# conrad.net
KiCad netlist of a schematic drawn in EAGLE
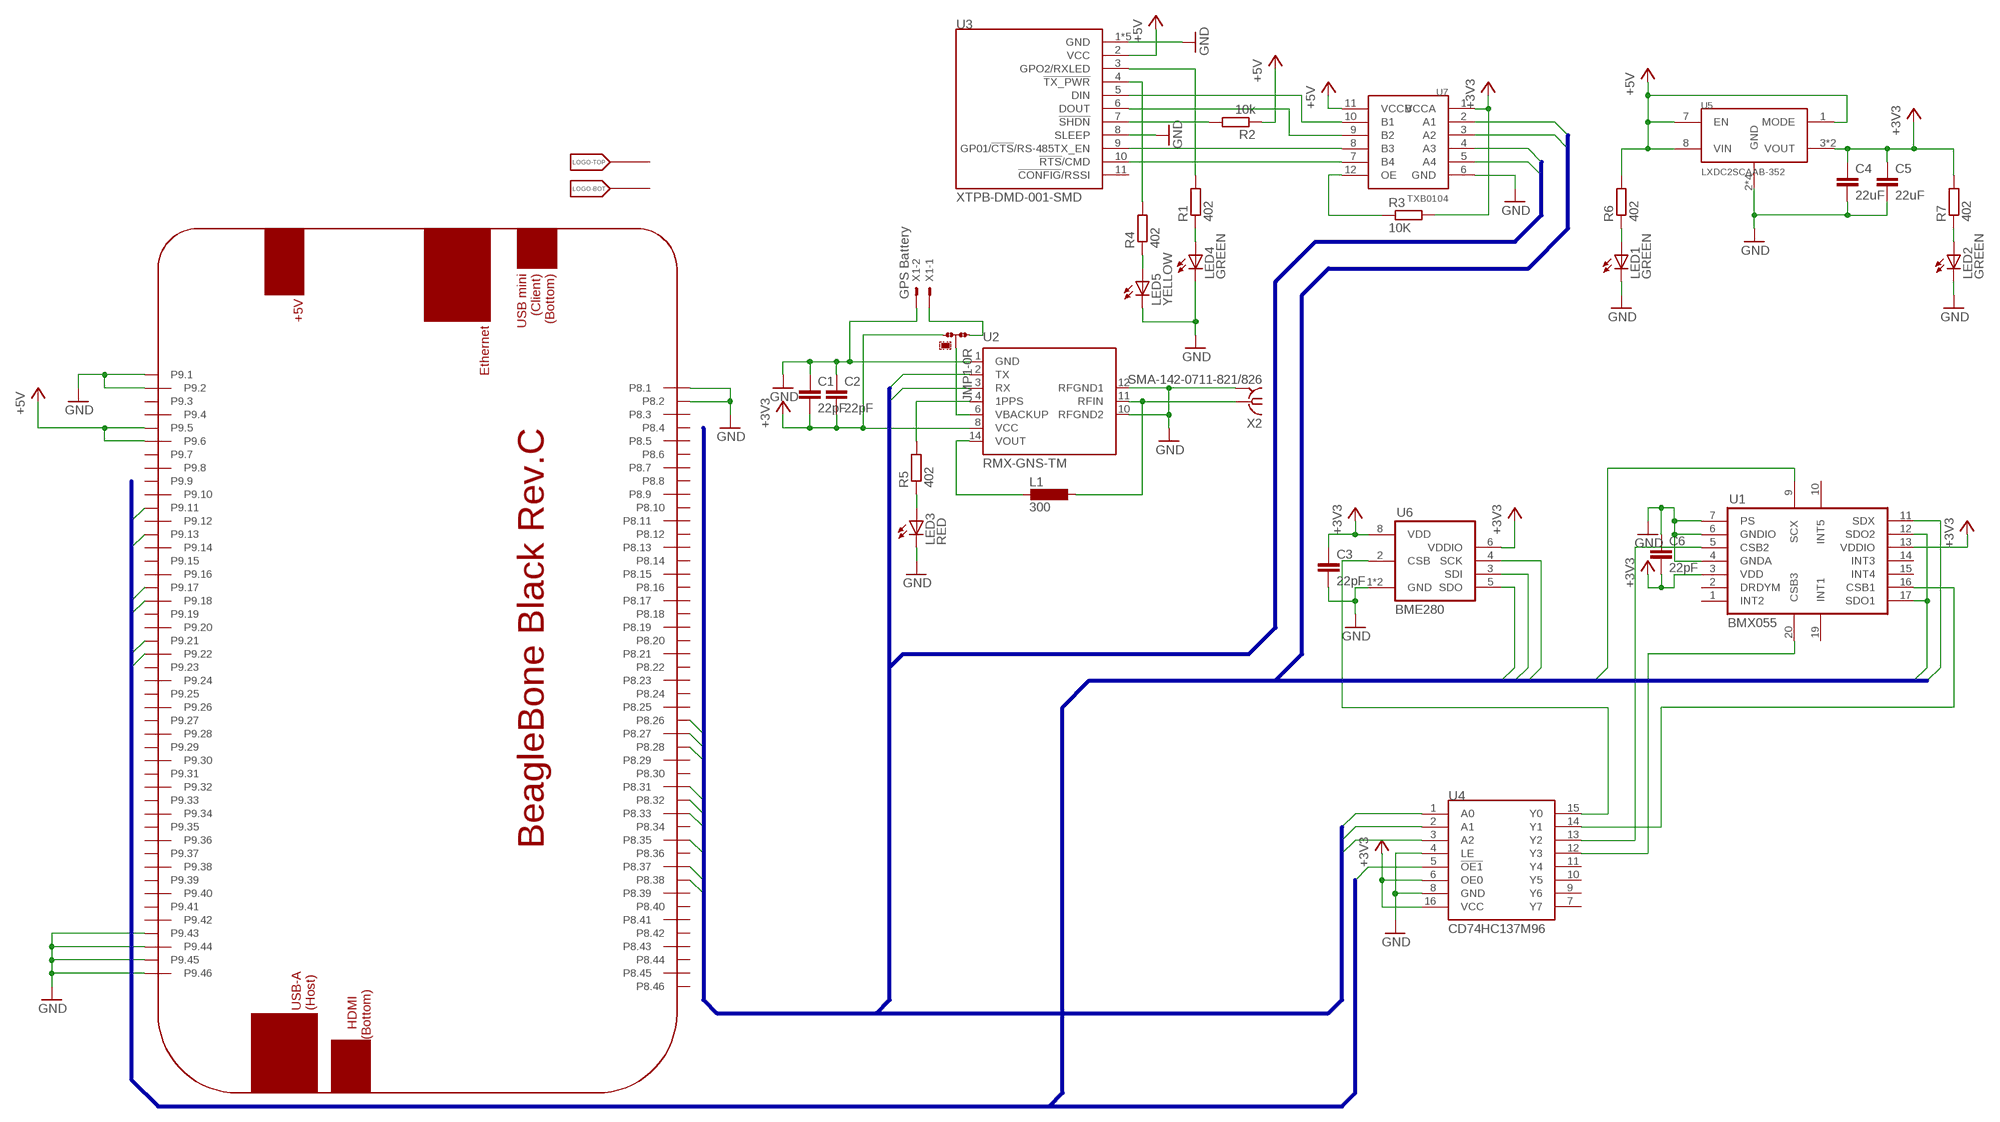
[diagram p0: schematic, sheet 1]

(export (version "E")
  (design (tool "Eeschema 10.0.6"))
  (components
    (comp (ref "C1")
      (value "22pF")
      (footprint "eagle-import:C0603K")
      (libsource (lib "eagle-import") (part "C-EUC0603K"))
    )
    (comp (ref "C2")
      (value "22pF")
      (footprint "eagle-import:C0603K")
      (libsource (lib "eagle-import") (part "C-EUC0603K"))
    )
    (comp (ref "C3")
      (value "22pF")
      (footprint "eagle-import:C0603K")
      (libsource (lib "eagle-import") (part "C-EUC0603K"))
    )
    (comp (ref "C4")
      (value "22uF")
      (footprint "eagle-import:C0603K")
      (libsource (lib "eagle-import") (part "C-EUC0603K"))
    )
    (comp (ref "C5")
      (value "22uF")
      (footprint "eagle-import:C0603K")
      (libsource (lib "eagle-import") (part "C-EUC0603K"))
    )
    (comp (ref "C6")
      (value "22pF")
      (footprint "eagle-import:C0603K")
      (libsource (lib "eagle-import") (part "C-EUC0603K"))
    )
    (comp (ref "JMP1")
      (value "0R-JUMPB")
      (footprint "eagle-import:B0R-JMP")
      (libsource (lib "eagle-import") (part "0R-JUMPB"))
    )
    (comp (ref "L1")
      (value "300")
      (footprint "eagle-import:L0402")
      (libsource (lib "eagle-import") (part "L-EU"))
    )
    (comp (ref "LED1")
      (value "GREEN")
      (footprint "eagle-import:SML0805")
      (libsource (lib "eagle-import") (part "LEDSML0805"))
    )
    (comp (ref "LED2")
      (value "GREEN")
      (footprint "eagle-import:SML0805")
      (libsource (lib "eagle-import") (part "LEDSML0805"))
    )
    (comp (ref "LED3")
      (value "RED")
      (footprint "eagle-import:SML0805")
      (libsource (lib "eagle-import") (part "LEDSML0805"))
    )
    (comp (ref "LED4")
      (value "GREEN")
      (footprint "eagle-import:SML0805")
      (libsource (lib "eagle-import") (part "LEDSML0805"))
    )
    (comp (ref "LED5")
      (value "YELLOW")
      (footprint "eagle-import:SML0805")
      (libsource (lib "eagle-import") (part "LEDSML0805"))
    )
    (comp (ref "LOGO")
      (value "SU_LOGO-DUMMY")
      (footprint "eagle-import:SU_LOGO_DS")
      (libsource (lib "eagle-import") (part "SU_LOGO-DUMMY"))
    )
    (comp (ref "PCB1")
      (value "BEAGLEBONE_BLACK_CAPE")
      (footprint "eagle-import:BEAGLEBONE_BLACK_CAPE")
      (libsource (lib "eagle-import") (part "BEAGLEBONE_BLACK_CAPE"))
    )
    (comp (ref "R1")
      (value "402")
      (footprint "eagle-import:R0603")
      (libsource (lib "eagle-import") (part "R-EU_R0603"))
    )
    (comp (ref "R2")
      (value "10k")
      (footprint "eagle-import:R0603")
      (libsource (lib "eagle-import") (part "R-EU_R0603"))
    )
    (comp (ref "R3")
      (value "10K")
      (footprint "eagle-import:R0603")
      (libsource (lib "eagle-import") (part "R-EU_R0603"))
    )
    (comp (ref "R4")
      (value "402")
      (footprint "eagle-import:R0603")
      (libsource (lib "eagle-import") (part "R-EU_R0603"))
    )
    (comp (ref "R5")
      (value "402")
      (footprint "eagle-import:R0603")
      (libsource (lib "eagle-import") (part "R-EU_R0603"))
    )
    (comp (ref "R6")
      (value "402")
      (footprint "eagle-import:R0603")
      (libsource (lib "eagle-import") (part "R-EU_R0603"))
    )
    (comp (ref "R7")
      (value "402")
      (footprint "eagle-import:R0603")
      (libsource (lib "eagle-import") (part "R-EU_R0603"))
    )
    (comp (ref "U1")
      (value "BMX055")
      (footprint "eagle-import:BMX055")
      (libsource (lib "eagle-import") (part "BMX055"))
    )
    (comp (ref "U2")
      (value "RMX-GNS-TM")
      (footprint "eagle-import:RMX-GNSS-TM")
      (libsource (lib "eagle-import") (part "RMX-GNS-TM"))
    )
    (comp (ref "U3")
      (value "XTPB-DMD-001-SMD")
      (footprint "eagle-import:XTP9B-DMS-001-SMD")
      (libsource (lib "eagle-import") (part "XTPB-DMD-001-SMD"))
    )
    (comp (ref "U4")
      (value "CD74HC137M96")
      (footprint "eagle-import:SO-16")
      (libsource (lib "eagle-import") (part "CD74HC237M96"))
    )
    (comp (ref "U5")
      (value "LXDC2SCAAB-352")
      (footprint "eagle-import:LXDC2SCAAB-352")
      (libsource (lib "eagle-import") (part "LXDC2SCAAB-352"))
    )
    (comp (ref "U6")
      (value "BME280")
      (footprint "eagle-import:BME280")
      (libsource (lib "eagle-import") (part "BME280"))
    )
    (comp (ref "U7")
      (value "TXB0104")
      (footprint "eagle-import:R-PUQFN-N12")
      (libsource (lib "eagle-import") (part "TXB0104"))
    )
    (comp (ref "X1")
      (value "GPS Battery")
      (footprint "eagle-import:15-91-02")
      (libsource (lib "eagle-import") (part "C-GRID-02-15-19"))
    )
    (comp (ref "X2")
      (value "SMA-142-0711-821/826")
      (footprint "eagle-import:J502-ND-142-0711-821_826")
      (fields (field (name "MF") "JOHNSON COMPONENTS") (field (name "MPN") "142-0711-821"))
      (libsource (lib "eagle-import") (part "SMA-142-0711-821/826"))
    )
  )
  (nets
    (net (code "1") (name "+3V3") (class "Default")
      (node (ref "C1") (pin "2") (pinfunction "2_2") (pintype "passive"))
      (node (ref "C2") (pin "2") (pinfunction "2_2") (pintype "passive"))
      (node (ref "C3") (pin "1") (pinfunction "1_1") (pintype "passive"))
      (node (ref "C4") (pin "1") (pinfunction "1_1") (pintype "passive"))
      (node (ref "C5") (pin "1") (pinfunction "1_1") (pintype "passive"))
      (node (ref "C6") (pin "2") (pinfunction "2_2") (pintype "passive"))
      (node (ref "JMP1") (pin "3") (pinfunction "3_3") (pintype "passive"))
      (node (ref "R3") (pin "2") (pinfunction "2_2") (pintype "passive"))
      (node (ref "R7") (pin "2") (pinfunction "2_2") (pintype "passive"))
      (node (ref "U1") (pin "13") (pinfunction "VDDIO_13") (pintype "power_in"))
      (node (ref "U1") (pin "3") (pinfunction "VDD_3") (pintype "power_in"))
      (node (ref "U2") (pin "8") (pinfunction "VCC_8") (pintype "power_in"))
      (node (ref "U4") (pin "16") (pinfunction "VCC_16") (pintype "power_in"))
      (node (ref "U4") (pin "6") (pinfunction "OE0_6") (pintype "input"))
      (node (ref "U5") (pin "3") (pinfunction "VOUT_3") (pintype "power_in"))
      (node (ref "U5") (pin "4") (pinfunction "VOUT_4") (pintype "power_in"))
      (node (ref "U6") (pin "6") (pinfunction "VDDIO_6") (pintype "power_in"))
      (node (ref "U6") (pin "8") (pinfunction "VDD_8") (pintype "power_in"))
      (node (ref "U7") (pin "1") (pinfunction "VCCA_1") (pintype "power_in"))
    )
    (net (code "2") (name "+5V") (class "Default")
      (node (ref "PCB1") (pin "P9.5") (pinfunction "P9.5_P9.5") (pintype "bidirectional"))
      (node (ref "PCB1") (pin "P9.6") (pinfunction "P9.6_P9.6") (pintype "bidirectional"))
      (node (ref "R2") (pin "1") (pinfunction "1_1") (pintype "passive"))
      (node (ref "R6") (pin "2") (pinfunction "2_2") (pintype "passive"))
      (node (ref "U3") (pin "2") (pinfunction "VCC_2") (pintype "power_in"))
      (node (ref "U5") (pin "1") (pinfunction "MODE_1") (pintype "input"))
      (node (ref "U5") (pin "7") (pinfunction "EN_7") (pintype "input"))
      (node (ref "U5") (pin "8") (pinfunction "VIN_8") (pintype "power_in"))
      (node (ref "U7") (pin "11") (pinfunction "VCCB_11") (pintype "power_in"))
    )
    (net (code "3") (name "/SPI0_CS0") (class "Default")
      (node (ref "PCB1") (pin "P9.17") (pinfunction "P9.17_P9.17") (pintype "bidirectional"))
      (node (ref "U4") (pin "5") (pinfunction "~{OE1}_5") (pintype "input"))
    )
    (net (code "4") (name "/SPI0_D0") (class "Default")
      (node (ref "PCB1") (pin "P9.21") (pinfunction "P9.21_P9.21") (pintype "bidirectional"))
      (node (ref "U1") (pin "12") (pinfunction "SDO2_12") (pintype "output"))
      (node (ref "U1") (pin "17") (pinfunction "SDO1_17") (pintype "output"))
      (node (ref "U6") (pin "5") (pinfunction "SDO_5") (pintype "input"))
    )
    (net (code "5") (name "/SPI0_D1") (class "Default")
      (node (ref "PCB1") (pin "P9.18") (pinfunction "P9.18_P9.18") (pintype "bidirectional"))
      (node (ref "U1") (pin "11") (pinfunction "SDX_11") (pintype "bidirectional"))
      (node (ref "U6") (pin "3") (pinfunction "SDI_3") (pintype "bidirectional"))
    )
    (net (code "6") (name "/SPI0_SCLK") (class "Default")
      (node (ref "PCB1") (pin "P9.22") (pinfunction "P9.22_P9.22") (pintype "bidirectional"))
      (node (ref "U1") (pin "9") (pinfunction "SCX_9") (pintype "input"))
      (node (ref "U6") (pin "4") (pinfunction "SCK_4") (pintype "bidirectional"))
    )
    (net (code "7") (name "/SPI_CSB26") (class "Default")
      (node (ref "PCB1") (pin "P8.26") (pinfunction "P8.26_P8.26") (pintype "bidirectional"))
      (node (ref "U4") (pin "1") (pinfunction "A0_1") (pintype "input"))
    )
    (net (code "8") (name "/SPI_CSB27") (class "Default")
      (node (ref "PCB1") (pin "P8.27") (pinfunction "P8.27_P8.27") (pintype "bidirectional"))
      (node (ref "U4") (pin "2") (pinfunction "A1_2") (pintype "input"))
    )
    (net (code "9") (name "/SPI_CSB28") (class "Default")
      (node (ref "PCB1") (pin "P8.28") (pinfunction "P8.28_P8.28") (pintype "bidirectional"))
      (node (ref "U4") (pin "3") (pinfunction "A2_3") (pintype "input"))
    )
    (net (code "10") (name "/UART4_CTSN") (class "Default")
      (node (ref "PCB1") (pin "P8.35") (pinfunction "P8.35_P8.35") (pintype "bidirectional"))
      (node (ref "U7") (pin "4") (pinfunction "A3_4") (pintype "bidirectional"))
    )
    (net (code "11") (name "/UART4_RTSN") (class "Default")
      (node (ref "PCB1") (pin "P8.33") (pinfunction "P8.33_P8.33") (pintype "bidirectional"))
      (node (ref "U7") (pin "5") (pinfunction "A4_5") (pintype "bidirectional"))
    )
    (net (code "12") (name "/UART4_RXD") (class "Default")
      (node (ref "PCB1") (pin "P9.11") (pinfunction "P9.11_P9.11") (pintype "bidirectional"))
      (node (ref "U7") (pin "3") (pinfunction "A2_3") (pintype "bidirectional"))
    )
    (net (code "13") (name "/UART4_TXD") (class "Default")
      (node (ref "PCB1") (pin "P9.13") (pinfunction "P9.13_P9.13") (pintype "bidirectional"))
      (node (ref "U7") (pin "2") (pinfunction "A1_2") (pintype "bidirectional"))
    )
    (net (code "14") (name "/UART5_RXD") (class "Default")
      (node (ref "PCB1") (pin "P8.38") (pinfunction "P8.38_P8.38") (pintype "bidirectional"))
      (node (ref "U2") (pin "2") (pinfunction "TX_2") (pintype "output"))
    )
    (net (code "15") (name "/UART5_TXD") (class "Default")
      (node (ref "PCB1") (pin "P8.37") (pinfunction "P8.37_P8.37") (pintype "bidirectional"))
      (node (ref "U2") (pin "3") (pinfunction "RX_3") (pintype "input"))
    )
    (net (code "16") (name "GND") (class "Default")
      (node (ref "C1") (pin "1") (pinfunction "1_1") (pintype "passive"))
      (node (ref "C2") (pin "1") (pinfunction "1_1") (pintype "passive"))
      (node (ref "C3") (pin "2") (pinfunction "2_2") (pintype "passive"))
      (node (ref "C4") (pin "2") (pinfunction "2_2") (pintype "passive"))
      (node (ref "C5") (pin "2") (pinfunction "2_2") (pintype "passive"))
      (node (ref "C6") (pin "1") (pinfunction "1_1") (pintype "passive"))
      (node (ref "LED1") (pin "C") (pinfunction "C_C") (pintype "passive"))
      (node (ref "LED2") (pin "C") (pinfunction "C_C") (pintype "passive"))
      (node (ref "LED3") (pin "C") (pinfunction "C_C") (pintype "passive"))
      (node (ref "LED4") (pin "C") (pinfunction "C_C") (pintype "passive"))
      (node (ref "LED5") (pin "C") (pinfunction "C_C") (pintype "passive"))
      (node (ref "PCB1") (pin "P8.1") (pinfunction "P8.1_P8.1") (pintype "bidirectional"))
      (node (ref "PCB1") (pin "P8.2") (pinfunction "P8.2_P8.2") (pintype "bidirectional"))
      (node (ref "PCB1") (pin "P9.1") (pinfunction "P9.1_P9.1") (pintype "bidirectional"))
      (node (ref "PCB1") (pin "P9.2") (pinfunction "P9.2_P9.2") (pintype "bidirectional"))
      (node (ref "PCB1") (pin "P9.43") (pinfunction "P9.43_P9.43") (pintype "bidirectional"))
      (node (ref "PCB1") (pin "P9.44") (pinfunction "P9.44_P9.44") (pintype "bidirectional"))
      (node (ref "PCB1") (pin "P9.45") (pinfunction "P9.45_P9.45") (pintype "bidirectional"))
      (node (ref "PCB1") (pin "P9.46") (pinfunction "P9.46_P9.46") (pintype "bidirectional"))
      (node (ref "U1") (pin "4") (pinfunction "GNDA_4") (pintype "power_in"))
      (node (ref "U1") (pin "6") (pinfunction "GNDIO_6") (pintype "bidirectional"))
      (node (ref "U1") (pin "7") (pinfunction "PS_7") (pintype "input"))
      (node (ref "U2") (pin "1") (pinfunction "GND_1") (pintype "power_in"))
      (node (ref "U2") (pin "10") (pinfunction "RFGND2_10") (pintype "power_in"))
      (node (ref "U2") (pin "12") (pinfunction "RFGND1_12") (pintype "power_in"))
      (node (ref "U3") (pin "1") (pinfunction "GND_1") (pintype "power_in"))
      (node (ref "U3") (pin "8") (pinfunction "SLEEP_8") (pintype "input"))
      (node (ref "U3") (pin "P$1") (pinfunction "GND_P$1") (pintype "power_in"))
      (node (ref "U3") (pin "P$2") (pinfunction "GND_P$2") (pintype "power_in"))
      (node (ref "U3") (pin "P$3") (pinfunction "GND_P$3") (pintype "power_in"))
      (node (ref "U3") (pin "P$4") (pinfunction "GND_P$4") (pintype "power_in"))
      (node (ref "U4") (pin "4") (pinfunction "LE_4") (pintype "input"))
      (node (ref "U4") (pin "8") (pinfunction "GND_8") (pintype "power_in"))
      (node (ref "U5") (pin "2") (pinfunction "GND_2") (pintype "power_in"))
      (node (ref "U5") (pin "5") (pinfunction "GND_5") (pintype "power_in"))
      (node (ref "U5") (pin "6") (pinfunction "GND_6") (pintype "power_in"))
      (node (ref "U5") (pin "9") (pinfunction "GND_9") (pintype "power_in"))
      (node (ref "U6") (pin "1") (pinfunction "GND_1") (pintype "power_in"))
      (node (ref "U6") (pin "7") (pinfunction "GND_7") (pintype "power_in"))
      (node (ref "U7") (pin "6") (pinfunction "GND_6") (pintype "power_in"))
      (node (ref "X1") (pin "2") (pinfunction "S_2") (pintype "passive"))
      (node (ref "X2") (pin "G@1") (pinfunction "2_G@1") (pintype "passive"))
      (node (ref "X2") (pin "G@2") (pinfunction "2_G@2") (pintype "passive"))
      (node (ref "X2") (pin "G@3") (pinfunction "2_G@3") (pintype "passive"))
      (node (ref "X2") (pin "G@4") (pinfunction "2_G@4") (pintype "passive"))
    )
    (net (code "17") (name "Net-(LED1-PadA)") (class "Default")
      (node (ref "LED1") (pin "A") (pinfunction "A_A") (pintype "passive"))
      (node (ref "R6") (pin "1") (pinfunction "1_1") (pintype "passive"))
    )
    (net (code "18") (name "Net-(LED2-PadA)") (class "Default")
      (node (ref "LED2") (pin "A") (pinfunction "A_A") (pintype "passive"))
      (node (ref "R7") (pin "1") (pinfunction "1_1") (pintype "passive"))
    )
    (net (code "19") (name "Net-(LED3-PadA)") (class "Default")
      (node (ref "LED3") (pin "A") (pinfunction "A_A") (pintype "passive"))
      (node (ref "R5") (pin "1") (pinfunction "1_1") (pintype "passive"))
    )
    (net (code "20") (name "Net-(LED4-PadA)") (class "Default")
      (node (ref "LED4") (pin "A") (pinfunction "A_A") (pintype "passive"))
      (node (ref "R1") (pin "1") (pinfunction "1_1") (pintype "passive"))
    )
    (net (code "21") (name "Net-(LED5-PadA)") (class "Default")
      (node (ref "LED5") (pin "A") (pinfunction "A_A") (pintype "passive"))
      (node (ref "R4") (pin "1") (pinfunction "1_1") (pintype "passive"))
    )
    (net (code "22") (name "Net-(U1-CSB1)") (class "Default")
      (node (ref "U1") (pin "16") (pinfunction "CSB1_16") (pintype "input"))
      (node (ref "U4") (pin "14") (pinfunction "Y1_14") (pintype "output"))
    )
    (net (code "23") (name "Net-(U1-CSB2)") (class "Default")
      (node (ref "U1") (pin "5") (pinfunction "CSB2_5") (pintype "input"))
      (node (ref "U4") (pin "13") (pinfunction "Y2_13") (pintype "output"))
    )
    (net (code "24") (name "Net-(U1-CSB3)") (class "Default")
      (node (ref "U1") (pin "20") (pinfunction "CSB3_20") (pintype "input"))
      (node (ref "U4") (pin "12") (pinfunction "Y3_12") (pintype "output"))
    )
    (net (code "25") (name "Net-(U2-1PPS)") (class "Default")
      (node (ref "R5") (pin "2") (pinfunction "2_2") (pintype "passive"))
      (node (ref "U2") (pin "4") (pinfunction "1PPS_4") (pintype "output"))
    )
    (net (code "26") (name "Net-(U2-RFIN)") (class "Default")
      (node (ref "L1") (pin "1") (pinfunction "1_1") (pintype "passive"))
      (node (ref "U2") (pin "11") (pinfunction "RFIN_11") (pintype "input"))
      (node (ref "X2") (pin "1") (pinfunction "1_1") (pintype "passive"))
    )
    (net (code "27") (name "Net-(U2-VBACKUP)") (class "Default")
      (node (ref "JMP1") (pin "2") (pinfunction "2_2") (pintype "passive"))
      (node (ref "U2") (pin "6") (pinfunction "VBACKUP_6") (pintype "power_in"))
    )
    (net (code "28") (name "Net-(U2-VOUT)") (class "Default")
      (node (ref "L1") (pin "2") (pinfunction "2_2") (pintype "passive"))
      (node (ref "U2") (pin "14") (pinfunction "VOUT_14") (pintype "output"))
    )
    (net (code "29") (name "Net-(U3-DIN)") (class "Default")
      (node (ref "U3") (pin "5") (pinfunction "DIN_5") (pintype "input"))
      (node (ref "U7") (pin "10") (pinfunction "B1_10") (pintype "bidirectional"))
    )
    (net (code "30") (name "Net-(U3-DOUT)") (class "Default")
      (node (ref "U3") (pin "6") (pinfunction "DOUT_6") (pintype "output"))
      (node (ref "U7") (pin "9") (pinfunction "B2_9") (pintype "bidirectional"))
    )
    (net (code "31") (name "Net-(U3-GP01{slash}~{CTS}{slash}RS-485TX_EN)") (class "Default")
      (node (ref "U3") (pin "9") (pinfunction "GP01/~{CTS}/RS-485TX_EN_9") (pintype "output"))
      (node (ref "U7") (pin "8") (pinfunction "B3_8") (pintype "bidirectional"))
    )
    (net (code "32") (name "Net-(U3-GPO2{slash}RXLED)") (class "Default")
      (node (ref "R1") (pin "2") (pinfunction "2_2") (pintype "passive"))
      (node (ref "U3") (pin "3") (pinfunction "GPO2/RXLED_3") (pintype "output"))
    )
    (net (code "33") (name "Net-(U3-~{RTS}{slash}CMD)") (class "Default")
      (node (ref "U3") (pin "10") (pinfunction "~{RTS}/CMD_10") (pintype "input"))
      (node (ref "U7") (pin "7") (pinfunction "B4_7") (pintype "bidirectional"))
    )
    (net (code "34") (name "Net-(U3-~{SHDN})") (class "Default")
      (node (ref "R2") (pin "2") (pinfunction "2_2") (pintype "passive"))
      (node (ref "U3") (pin "7") (pinfunction "~{SHDN}_7") (pintype "input"))
    )
    (net (code "35") (name "Net-(U3-~{TX_PWR})") (class "Default")
      (node (ref "R4") (pin "2") (pinfunction "2_2") (pintype "passive"))
      (node (ref "U3") (pin "4") (pinfunction "~{TX_PWR}_4") (pintype "output"))
    )
    (net (code "36") (name "Net-(U4-Y0)") (class "Default")
      (node (ref "U4") (pin "15") (pinfunction "Y0_15") (pintype "output"))
      (node (ref "U6") (pin "2") (pinfunction "CSB_2") (pintype "input"))
    )
    (net (code "37") (name "Net-(U7-OE)") (class "Default")
      (node (ref "R3") (pin "1") (pinfunction "1_1") (pintype "passive"))
      (node (ref "U7") (pin "12") (pinfunction "OE_12") (pintype "input"))
    )
    (net (code "38") (name "Net-(X1A-S)") (class "Default")
      (node (ref "JMP1") (pin "1") (pinfunction "1_1") (pintype "passive"))
      (node (ref "X1") (pin "1") (pinfunction "S_1") (pintype "passive"))
    )
    (net (code "39") (name "unconnected-(LOGO-PadP$1)") (class "Default")
      (node (ref "LOGO") (pin "P$1") (pinfunction "P$1_P$1") (pintype "bidirectional"))
    )
    (net (code "40") (name "unconnected-(LOGOA-P$1-PadP$2)") (class "Default")
      (node (ref "LOGO") (pin "P$2") (pinfunction "P$1_P$2") (pintype "bidirectional"))
    )
    (net (code "41") (name "unconnected-(PCB1-PadP8.3)") (class "Default")
      (node (ref "PCB1") (pin "P8.3") (pinfunction "P8.3_P8.3") (pintype "bidirectional"))
    )
    (net (code "42") (name "unconnected-(PCB1-PadP8.4)") (class "Default")
      (node (ref "PCB1") (pin "P8.4") (pinfunction "P8.4_P8.4") (pintype "bidirectional"))
    )
    (net (code "43") (name "unconnected-(PCB1-PadP8.5)") (class "Default")
      (node (ref "PCB1") (pin "P8.5") (pinfunction "P8.5_P8.5") (pintype "bidirectional"))
    )
    (net (code "44") (name "unconnected-(PCB1-PadP8.6)") (class "Default")
      (node (ref "PCB1") (pin "P8.6") (pinfunction "P8.6_P8.6") (pintype "bidirectional"))
    )
    (net (code "45") (name "unconnected-(PCB1-PadP8.7)") (class "Default")
      (node (ref "PCB1") (pin "P8.7") (pinfunction "P8.7_P8.7") (pintype "bidirectional"))
    )
    (net (code "46") (name "unconnected-(PCB1-PadP8.8)") (class "Default")
      (node (ref "PCB1") (pin "P8.8") (pinfunction "P8.8_P8.8") (pintype "bidirectional"))
    )
    (net (code "47") (name "unconnected-(PCB1-PadP8.9)") (class "Default")
      (node (ref "PCB1") (pin "P8.9") (pinfunction "P8.9_P8.9") (pintype "bidirectional"))
    )
    (net (code "48") (name "unconnected-(PCB1-PadP8.10)") (class "Default")
      (node (ref "PCB1") (pin "P8.10") (pinfunction "P8.10_P8.10") (pintype "bidirectional"))
    )
    (net (code "49") (name "unconnected-(PCB1-PadP8.11)") (class "Default")
      (node (ref "PCB1") (pin "P8.11") (pinfunction "P8.11_P8.11") (pintype "bidirectional"))
    )
    (net (code "50") (name "unconnected-(PCB1-PadP8.12)") (class "Default")
      (node (ref "PCB1") (pin "P8.12") (pinfunction "P8.12_P8.12") (pintype "bidirectional"))
    )
    (net (code "51") (name "unconnected-(PCB1-PadP8.13)") (class "Default")
      (node (ref "PCB1") (pin "P8.13") (pinfunction "P8.13_P8.13") (pintype "bidirectional"))
    )
    (net (code "52") (name "unconnected-(PCB1-PadP8.14)") (class "Default")
      (node (ref "PCB1") (pin "P8.14") (pinfunction "P8.14_P8.14") (pintype "bidirectional"))
    )
    (net (code "53") (name "unconnected-(PCB1-PadP8.15)") (class "Default")
      (node (ref "PCB1") (pin "P8.15") (pinfunction "P8.15_P8.15") (pintype "bidirectional"))
    )
    (net (code "54") (name "unconnected-(PCB1-PadP8.16)") (class "Default")
      (node (ref "PCB1") (pin "P8.16") (pinfunction "P8.16_P8.16") (pintype "bidirectional"))
    )
    (net (code "55") (name "unconnected-(PCB1-PadP8.17)") (class "Default")
      (node (ref "PCB1") (pin "P8.17") (pinfunction "P8.17_P8.17") (pintype "bidirectional"))
    )
    (net (code "56") (name "unconnected-(PCB1-PadP8.18)") (class "Default")
      (node (ref "PCB1") (pin "P8.18") (pinfunction "P8.18_P8.18") (pintype "bidirectional"))
    )
    (net (code "57") (name "unconnected-(PCB1-PadP8.19)") (class "Default")
      (node (ref "PCB1") (pin "P8.19") (pinfunction "P8.19_P8.19") (pintype "bidirectional"))
    )
    (net (code "58") (name "unconnected-(PCB1-PadP8.20)") (class "Default")
      (node (ref "PCB1") (pin "P8.20") (pinfunction "P8.20_P8.20") (pintype "bidirectional"))
    )
    (net (code "59") (name "unconnected-(PCB1-PadP8.21)") (class "Default")
      (node (ref "PCB1") (pin "P8.21") (pinfunction "P8.21_P8.21") (pintype "bidirectional"))
    )
    (net (code "60") (name "unconnected-(PCB1-PadP8.22)") (class "Default")
      (node (ref "PCB1") (pin "P8.22") (pinfunction "P8.22_P8.22") (pintype "bidirectional"))
    )
    (net (code "61") (name "unconnected-(PCB1-PadP8.23)") (class "Default")
      (node (ref "PCB1") (pin "P8.23") (pinfunction "P8.23_P8.23") (pintype "bidirectional"))
    )
    (net (code "62") (name "unconnected-(PCB1-PadP8.24)") (class "Default")
      (node (ref "PCB1") (pin "P8.24") (pinfunction "P8.24_P8.24") (pintype "bidirectional"))
    )
    (net (code "63") (name "unconnected-(PCB1-PadP8.25)") (class "Default")
      (node (ref "PCB1") (pin "P8.25") (pinfunction "P8.25_P8.25") (pintype "bidirectional"))
    )
    (net (code "64") (name "unconnected-(PCB1-PadP8.29)") (class "Default")
      (node (ref "PCB1") (pin "P8.29") (pinfunction "P8.29_P8.29") (pintype "bidirectional"))
    )
    (net (code "65") (name "unconnected-(PCB1-PadP8.30)") (class "Default")
      (node (ref "PCB1") (pin "P8.30") (pinfunction "P8.30_P8.30") (pintype "bidirectional"))
    )
    (net (code "66") (name "unconnected-(PCB1-PadP8.31)") (class "Default")
      (node (ref "PCB1") (pin "P8.31") (pinfunction "P8.31_P8.31") (pintype "bidirectional"))
    )
    (net (code "67") (name "unconnected-(PCB1-PadP8.32)") (class "Default")
      (node (ref "PCB1") (pin "P8.32") (pinfunction "P8.32_P8.32") (pintype "bidirectional"))
    )
    (net (code "68") (name "unconnected-(PCB1-PadP8.34)") (class "Default")
      (node (ref "PCB1") (pin "P8.34") (pinfunction "P8.34_P8.34") (pintype "bidirectional"))
    )
    (net (code "69") (name "unconnected-(PCB1-PadP8.36)") (class "Default")
      (node (ref "PCB1") (pin "P8.36") (pinfunction "P8.36_P8.36") (pintype "bidirectional"))
    )
    (net (code "70") (name "unconnected-(PCB1-PadP8.39)") (class "Default")
      (node (ref "PCB1") (pin "P8.39") (pinfunction "P8.39_P8.39") (pintype "bidirectional"))
    )
    (net (code "71") (name "unconnected-(PCB1-PadP8.40)") (class "Default")
      (node (ref "PCB1") (pin "P8.40") (pinfunction "P8.40_P8.40") (pintype "bidirectional"))
    )
    (net (code "72") (name "unconnected-(PCB1-PadP8.41)") (class "Default")
      (node (ref "PCB1") (pin "P8.41") (pinfunction "P8.41_P8.41") (pintype "bidirectional"))
    )
    (net (code "73") (name "unconnected-(PCB1-PadP8.42)") (class "Default")
      (node (ref "PCB1") (pin "P8.42") (pinfunction "P8.42_P8.42") (pintype "bidirectional"))
    )
    (net (code "74") (name "unconnected-(PCB1-PadP8.43)") (class "Default")
      (node (ref "PCB1") (pin "P8.43") (pinfunction "P8.43_P8.43") (pintype "bidirectional"))
    )
    (net (code "75") (name "unconnected-(PCB1-PadP8.44)") (class "Default")
      (node (ref "PCB1") (pin "P8.44") (pinfunction "P8.44_P8.44") (pintype "bidirectional"))
    )
    (net (code "76") (name "unconnected-(PCB1-PadP8.45)") (class "Default")
      (node (ref "PCB1") (pin "P8.45") (pinfunction "P8.45_P8.45") (pintype "bidirectional"))
    )
    (net (code "77") (name "unconnected-(PCB1-PadP8.46)") (class "Default")
      (node (ref "PCB1") (pin "P8.46") (pinfunction "P8.46_P8.46") (pintype "bidirectional"))
    )
    (net (code "78") (name "unconnected-(PCB1-PadP9.3)") (class "Default")
      (node (ref "PCB1") (pin "P9.3") (pinfunction "P9.3_P9.3") (pintype "bidirectional"))
    )
    (net (code "79") (name "unconnected-(PCB1-PadP9.4)") (class "Default")
      (node (ref "PCB1") (pin "P9.4") (pinfunction "P9.4_P9.4") (pintype "bidirectional"))
    )
    (net (code "80") (name "unconnected-(PCB1-PadP9.7)") (class "Default")
      (node (ref "PCB1") (pin "P9.7") (pinfunction "P9.7_P9.7") (pintype "bidirectional"))
    )
    (net (code "81") (name "unconnected-(PCB1-PadP9.8)") (class "Default")
      (node (ref "PCB1") (pin "P9.8") (pinfunction "P9.8_P9.8") (pintype "bidirectional"))
    )
    (net (code "82") (name "unconnected-(PCB1-PadP9.9)") (class "Default")
      (node (ref "PCB1") (pin "P9.9") (pinfunction "P9.9_P9.9") (pintype "bidirectional"))
    )
    (net (code "83") (name "unconnected-(PCB1-PadP9.10)") (class "Default")
      (node (ref "PCB1") (pin "P9.10") (pinfunction "P9.10_P9.10") (pintype "bidirectional"))
    )
    (net (code "84") (name "unconnected-(PCB1-PadP9.12)") (class "Default")
      (node (ref "PCB1") (pin "P9.12") (pinfunction "P9.12_P9.12") (pintype "bidirectional"))
    )
    (net (code "85") (name "unconnected-(PCB1-PadP9.14)") (class "Default")
      (node (ref "PCB1") (pin "P9.14") (pinfunction "P9.14_P9.14") (pintype "bidirectional"))
    )
    (net (code "86") (name "unconnected-(PCB1-PadP9.15)") (class "Default")
      (node (ref "PCB1") (pin "P9.15") (pinfunction "P9.15_P9.15") (pintype "bidirectional"))
    )
    (net (code "87") (name "unconnected-(PCB1-PadP9.16)") (class "Default")
      (node (ref "PCB1") (pin "P9.16") (pinfunction "P9.16_P9.16") (pintype "bidirectional"))
    )
    (net (code "88") (name "unconnected-(PCB1-PadP9.19)") (class "Default")
      (node (ref "PCB1") (pin "P9.19") (pinfunction "P9.19_P9.19") (pintype "bidirectional"))
    )
    (net (code "89") (name "unconnected-(PCB1-PadP9.20)") (class "Default")
      (node (ref "PCB1") (pin "P9.20") (pinfunction "P9.20_P9.20") (pintype "bidirectional"))
    )
    (net (code "90") (name "unconnected-(PCB1-PadP9.23)") (class "Default")
      (node (ref "PCB1") (pin "P9.23") (pinfunction "P9.23_P9.23") (pintype "bidirectional"))
    )
    (net (code "91") (name "unconnected-(PCB1-PadP9.24)") (class "Default")
      (node (ref "PCB1") (pin "P9.24") (pinfunction "P9.24_P9.24") (pintype "bidirectional"))
    )
    (net (code "92") (name "unconnected-(PCB1-PadP9.25)") (class "Default")
      (node (ref "PCB1") (pin "P9.25") (pinfunction "P9.25_P9.25") (pintype "bidirectional"))
    )
    (net (code "93") (name "unconnected-(PCB1-PadP9.26)") (class "Default")
      (node (ref "PCB1") (pin "P9.26") (pinfunction "P9.26_P9.26") (pintype "bidirectional"))
    )
    (net (code "94") (name "unconnected-(PCB1-PadP9.27)") (class "Default")
      (node (ref "PCB1") (pin "P9.27") (pinfunction "P9.27_P9.27") (pintype "bidirectional"))
    )
    (net (code "95") (name "unconnected-(PCB1-PadP9.28)") (class "Default")
      (node (ref "PCB1") (pin "P9.28") (pinfunction "P9.28_P9.28") (pintype "bidirectional"))
    )
    (net (code "96") (name "unconnected-(PCB1-PadP9.29)") (class "Default")
      (node (ref "PCB1") (pin "P9.29") (pinfunction "P9.29_P9.29") (pintype "bidirectional"))
    )
    (net (code "97") (name "unconnected-(PCB1-PadP9.30)") (class "Default")
      (node (ref "PCB1") (pin "P9.30") (pinfunction "P9.30_P9.30") (pintype "bidirectional"))
    )
    (net (code "98") (name "unconnected-(PCB1-PadP9.31)") (class "Default")
      (node (ref "PCB1") (pin "P9.31") (pinfunction "P9.31_P9.31") (pintype "bidirectional"))
    )
    (net (code "99") (name "unconnected-(PCB1-PadP9.32)") (class "Default")
      (node (ref "PCB1") (pin "P9.32") (pinfunction "P9.32_P9.32") (pintype "bidirectional"))
    )
    (net (code "100") (name "unconnected-(PCB1-PadP9.33)") (class "Default")
      (node (ref "PCB1") (pin "P9.33") (pinfunction "P9.33_P9.33") (pintype "bidirectional"))
    )
    (net (code "101") (name "unconnected-(PCB1-PadP9.34)") (class "Default")
      (node (ref "PCB1") (pin "P9.34") (pinfunction "P9.34_P9.34") (pintype "bidirectional"))
    )
    (net (code "102") (name "unconnected-(PCB1-PadP9.35)") (class "Default")
      (node (ref "PCB1") (pin "P9.35") (pinfunction "P9.35_P9.35") (pintype "bidirectional"))
    )
    (net (code "103") (name "unconnected-(PCB1-PadP9.36)") (class "Default")
      (node (ref "PCB1") (pin "P9.36") (pinfunction "P9.36_P9.36") (pintype "bidirectional"))
    )
    (net (code "104") (name "unconnected-(PCB1-PadP9.37)") (class "Default")
      (node (ref "PCB1") (pin "P9.37") (pinfunction "P9.37_P9.37") (pintype "bidirectional"))
    )
    (net (code "105") (name "unconnected-(PCB1-PadP9.38)") (class "Default")
      (node (ref "PCB1") (pin "P9.38") (pinfunction "P9.38_P9.38") (pintype "bidirectional"))
    )
    (net (code "106") (name "unconnected-(PCB1-PadP9.39)") (class "Default")
      (node (ref "PCB1") (pin "P9.39") (pinfunction "P9.39_P9.39") (pintype "bidirectional"))
    )
    (net (code "107") (name "unconnected-(PCB1-PadP9.40)") (class "Default")
      (node (ref "PCB1") (pin "P9.40") (pinfunction "P9.40_P9.40") (pintype "bidirectional"))
    )
    (net (code "108") (name "unconnected-(PCB1-PadP9.41)") (class "Default")
      (node (ref "PCB1") (pin "P9.41") (pinfunction "P9.41_P9.41") (pintype "bidirectional"))
    )
    (net (code "109") (name "unconnected-(PCB1-PadP9.42)") (class "Default")
      (node (ref "PCB1") (pin "P9.42") (pinfunction "P9.42_P9.42") (pintype "bidirectional"))
    )
    (net (code "110") (name "unconnected-(U1-DRDYM-Pad2)") (class "Default")
      (node (ref "U1") (pin "2") (pinfunction "DRDYM_2") (pintype "output"))
    )
    (net (code "111") (name "unconnected-(U1-INT1-Pad19)") (class "Default")
      (node (ref "U1") (pin "19") (pinfunction "INT1_19") (pintype "output"))
    )
    (net (code "112") (name "unconnected-(U1-INT2-Pad1)") (class "Default")
      (node (ref "U1") (pin "1") (pinfunction "INT2_1") (pintype "output"))
    )
    (net (code "113") (name "unconnected-(U1-INT3-Pad14)") (class "Default")
      (node (ref "U1") (pin "14") (pinfunction "INT3_14") (pintype "bidirectional"))
    )
    (net (code "114") (name "unconnected-(U1-INT4-Pad15)") (class "Default")
      (node (ref "U1") (pin "15") (pinfunction "INT4_15") (pintype "bidirectional"))
    )
    (net (code "115") (name "unconnected-(U1-INT5-Pad10)") (class "Default")
      (node (ref "U1") (pin "10") (pinfunction "INT5_10") (pintype "output"))
    )
    (net (code "116") (name "unconnected-(U3-~{CONFIG}{slash}RSSI-Pad11)") (class "Default")
      (node (ref "U3") (pin "11") (pinfunction "~{CONFIG}/RSSI_11") (pintype "bidirectional"))
    )
    (net (code "117") (name "unconnected-(U4-Y4-Pad11)") (class "Default")
      (node (ref "U4") (pin "11") (pinfunction "Y4_11") (pintype "output"))
    )
    (net (code "118") (name "unconnected-(U4-Y5-Pad10)") (class "Default")
      (node (ref "U4") (pin "10") (pinfunction "Y5_10") (pintype "output"))
    )
    (net (code "119") (name "unconnected-(U4-Y6-Pad9)") (class "Default")
      (node (ref "U4") (pin "9") (pinfunction "Y6_9") (pintype "output"))
    )
    (net (code "120") (name "unconnected-(U4-Y7-Pad7)") (class "Default")
      (node (ref "U4") (pin "7") (pinfunction "Y7_7") (pintype "output"))
    )
  )
)
